# sw63_mk3.net
KiCad netlist of a schematic drawn in EAGLE
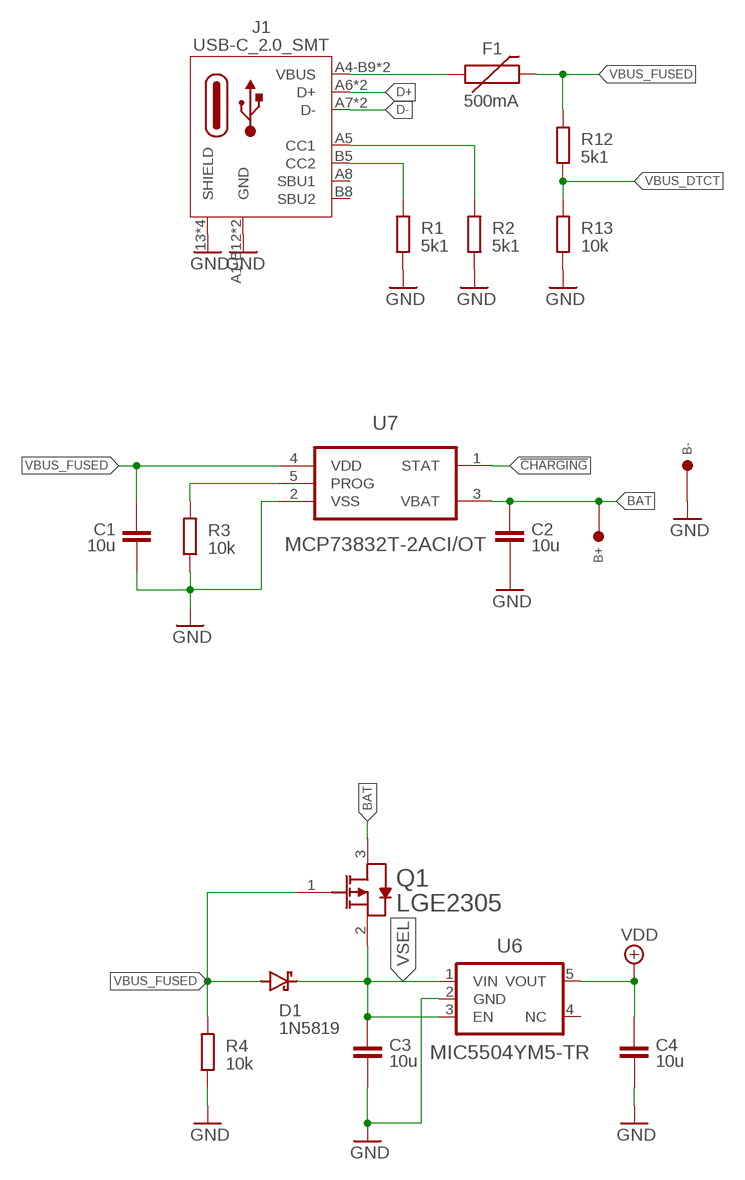
[diagram p0: schematic, sheet 1, part 1 of 2]
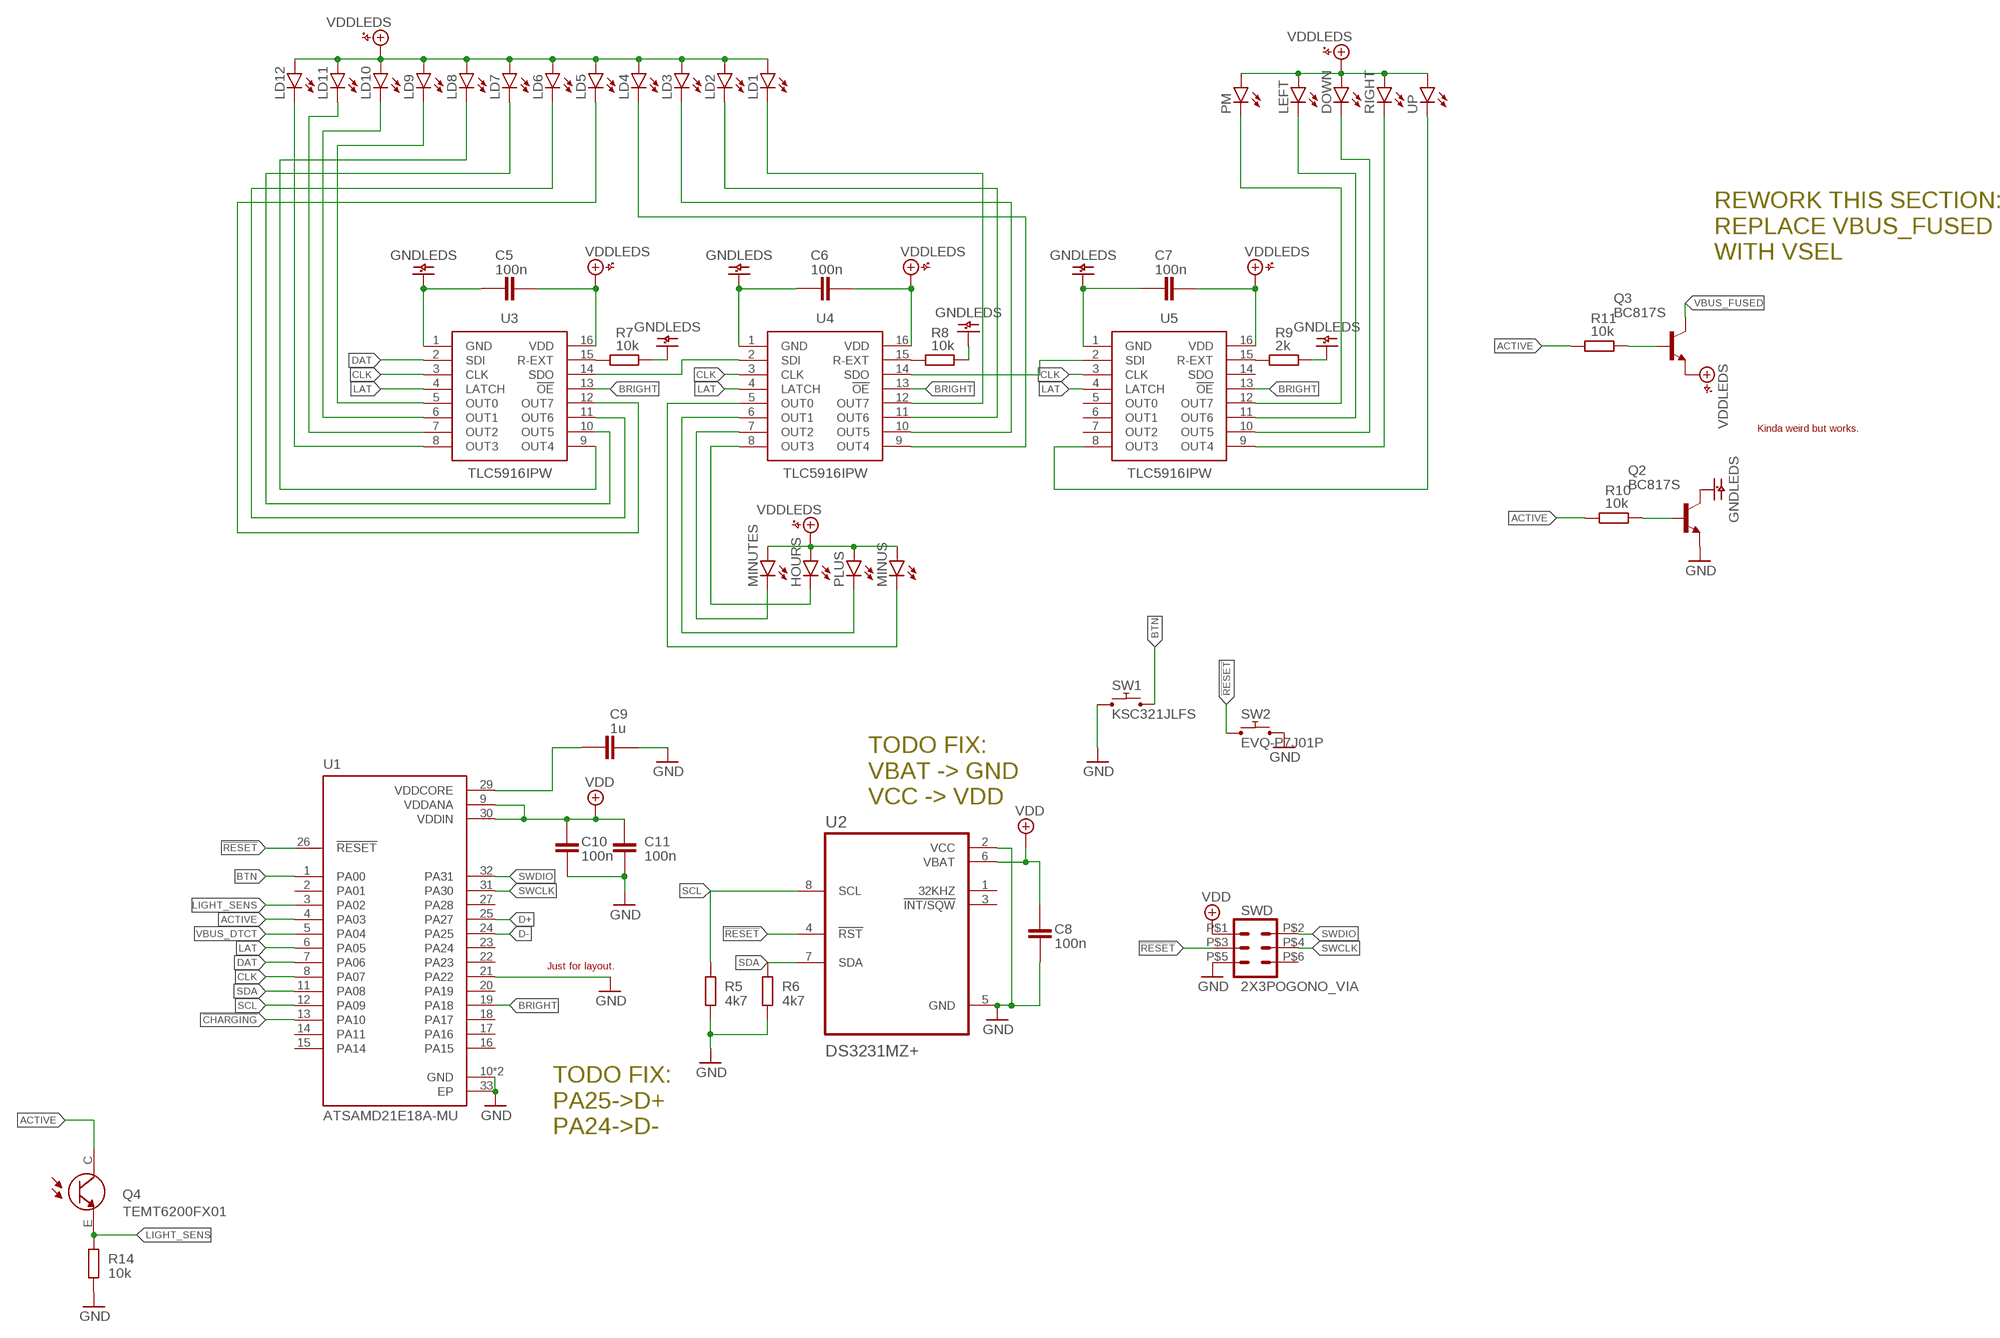
[diagram p1: schematic, sheet 1, part 2 of 2]

(export (version "E")
  (design (tool "Eeschema 10.0.6"))
  (components
    (comp (ref "B+")
      (value "TEST_PIN_LARGE")
      (footprint "eagle-import:TEST_PIN_2.0")
      (libsource (lib "eagle-import") (part "TEST_PIN_LARGE"))
    )
    (comp (ref "B-")
      (value "TEST_PIN_LARGE")
      (footprint "eagle-import:TEST_PIN_2.0")
      (libsource (lib "eagle-import") (part "TEST_PIN_LARGE"))
    )
    (comp (ref "C1")
      (value "10u")
      (footprint "eagle-import:CAPACITOR0805")
      (libsource (lib "eagle-import") (part "CAPACITOR0805"))
    )
    (comp (ref "C2")
      (value "10u")
      (footprint "eagle-import:CAPACITOR0805")
      (libsource (lib "eagle-import") (part "CAPACITOR0805"))
    )
    (comp (ref "C3")
      (value "10u")
      (footprint "eagle-import:CAPACITOR0805")
      (libsource (lib "eagle-import") (part "CAPACITOR0805"))
    )
    (comp (ref "C4")
      (value "10u")
      (footprint "eagle-import:CAPACITOR0805")
      (libsource (lib "eagle-import") (part "CAPACITOR0805"))
    )
    (comp (ref "C5")
      (value "100n")
      (footprint "eagle-import:CAPACITOR0603")
      (libsource (lib "eagle-import") (part "CAPACITOR0603"))
    )
    (comp (ref "C6")
      (value "100n")
      (footprint "eagle-import:CAPACITOR0603")
      (libsource (lib "eagle-import") (part "CAPACITOR0603"))
    )
    (comp (ref "C7")
      (value "100n")
      (footprint "eagle-import:CAPACITOR0603")
      (libsource (lib "eagle-import") (part "CAPACITOR0603"))
    )
    (comp (ref "C8")
      (value "100n")
      (footprint "eagle-import:CAPACITOR0603")
      (libsource (lib "eagle-import") (part "CAPACITOR0603"))
    )
    (comp (ref "C9")
      (value "1u")
      (footprint "eagle-import:CAPACITOR0603")
      (libsource (lib "eagle-import") (part "CAPACITOR0603"))
    )
    (comp (ref "C10")
      (value "100n")
      (footprint "eagle-import:CAPACITOR0603")
      (libsource (lib "eagle-import") (part "CAPACITOR0603"))
    )
    (comp (ref "C11")
      (value "100n")
      (footprint "eagle-import:CAPACITOR0603")
      (libsource (lib "eagle-import") (part "CAPACITOR0603"))
    )
    (comp (ref "D1")
      (value "1N5819")
      (footprint "eagle-import:SOD123")
      (libsource (lib "eagle-import") (part "SCHOTTKY_DIODE"))
    )
    (comp (ref "DOWN")
      (value "LED_RECT-3.2X2")
      (footprint "eagle-import:LED_RECT_3.2X2")
      (libsource (lib "eagle-import") (part "LED_RECT-3.2X2"))
    )
    (comp (ref "F1")
      (value "500mA")
      (footprint "eagle-import:PTC0805")
      (libsource (lib "eagle-import") (part "PTC"))
    )
    (comp (ref "HOURS")
      (value "LED_THT-5MM_B")
      (footprint "eagle-import:LED_5MM_BLUE")
      (libsource (lib "eagle-import") (part "LED_THT-5MM_B"))
    )
    (comp (ref "J1")
      (value "USB-C_2.0_SMT")
      (footprint "eagle-import:USB-C_FULL_SMT")
      (libsource (lib "eagle-import") (part "USB-C_2.0_SMT"))
    )
    (comp (ref "LD1")
      (value "LED_SMT_1206")
      (footprint "eagle-import:LED_1206")
      (libsource (lib "eagle-import") (part "LED_SMT_1206"))
    )
    (comp (ref "LD2")
      (value "LED_SMT_1206")
      (footprint "eagle-import:LED_1206")
      (libsource (lib "eagle-import") (part "LED_SMT_1206"))
    )
    (comp (ref "LD3")
      (value "LED_SMT_1206")
      (footprint "eagle-import:LED_1206")
      (libsource (lib "eagle-import") (part "LED_SMT_1206"))
    )
    (comp (ref "LD4")
      (value "LED_SMT_1206")
      (footprint "eagle-import:LED_1206")
      (libsource (lib "eagle-import") (part "LED_SMT_1206"))
    )
    (comp (ref "LD5")
      (value "LED_SMT_1206")
      (footprint "eagle-import:LED_1206")
      (libsource (lib "eagle-import") (part "LED_SMT_1206"))
    )
    (comp (ref "LD6")
      (value "LED_SMT_1206")
      (footprint "eagle-import:LED_1206")
      (libsource (lib "eagle-import") (part "LED_SMT_1206"))
    )
    (comp (ref "LD7")
      (value "LED_SMT_1206")
      (footprint "eagle-import:LED_1206")
      (libsource (lib "eagle-import") (part "LED_SMT_1206"))
    )
    (comp (ref "LD8")
      (value "LED_SMT_1206")
      (footprint "eagle-import:LED_1206")
      (libsource (lib "eagle-import") (part "LED_SMT_1206"))
    )
    (comp (ref "LD9")
      (value "LED_SMT_1206")
      (footprint "eagle-import:LED_1206")
      (libsource (lib "eagle-import") (part "LED_SMT_1206"))
    )
    (comp (ref "LD10")
      (value "LED_SMT_1206")
      (footprint "eagle-import:LED_1206")
      (libsource (lib "eagle-import") (part "LED_SMT_1206"))
    )
    (comp (ref "LD11")
      (value "LED_SMT_1206")
      (footprint "eagle-import:LED_1206")
      (libsource (lib "eagle-import") (part "LED_SMT_1206"))
    )
    (comp (ref "LD12")
      (value "LED_SMT_1206")
      (footprint "eagle-import:LED_1206")
      (libsource (lib "eagle-import") (part "LED_SMT_1206"))
    )
    (comp (ref "LEFT")
      (value "LED_RECT-3.2X2")
      (footprint "eagle-import:LED_RECT_3.2X2")
      (libsource (lib "eagle-import") (part "LED_RECT-3.2X2"))
    )
    (comp (ref "MINUS")
      (value "LED_THT-5MM_R")
      (footprint "eagle-import:LED_5MM_RED")
      (libsource (lib "eagle-import") (part "LED_THT-5MM_R"))
    )
    (comp (ref "MINUTES")
      (value "LED_THT-5MM_Y")
      (footprint "eagle-import:LED_5MM_YELLOW")
      (libsource (lib "eagle-import") (part "LED_THT-5MM_Y"))
    )
    (comp (ref "PLUS")
      (value "LED_THT-5MM_G")
      (footprint "eagle-import:LED_5MM_GREEN")
      (libsource (lib "eagle-import") (part "LED_THT-5MM_G"))
    )
    (comp (ref "PM")
      (value "LED_THT-3MM_ALT")
      (footprint "eagle-import:LED_3MM_ALT")
      (libsource (lib "eagle-import") (part "LED_THT-3MM_ALT"))
    )
    (comp (ref "Q1")
      (value "LGE2305")
      (footprint "eagle-import:SOT23")
      (libsource (lib "eagle-import") (part "LGE2305"))
    )
    (comp (ref "Q2")
      (value "BC817S")
      (footprint "eagle-import:SOT23")
      (libsource (lib "eagle-import") (part "BC817S"))
    )
    (comp (ref "Q3")
      (value "BC817S")
      (footprint "eagle-import:SOT23")
      (libsource (lib "eagle-import") (part "BC817S"))
    )
    (comp (ref "Q4")
      (value "TEMT6200FX01")
      (footprint "eagle-import:TEMT6200FX01")
      (fields (field (name "MF") "Vishay Semiconductor"))
      (libsource (lib "eagle-import") (part "TEMT6200FX01"))
    )
    (comp (ref "R1")
      (value "5k1")
      (footprint "eagle-import:RESISTOR0603")
      (libsource (lib "eagle-import") (part "RESISTOR0603"))
    )
    (comp (ref "R2")
      (value "5k1")
      (footprint "eagle-import:RESISTOR0603")
      (libsource (lib "eagle-import") (part "RESISTOR0603"))
    )
    (comp (ref "R3")
      (value "10k")
      (footprint "eagle-import:RESISTOR0603")
      (libsource (lib "eagle-import") (part "RESISTOR0603"))
    )
    (comp (ref "R4")
      (value "10k")
      (footprint "eagle-import:RESISTOR0603")
      (libsource (lib "eagle-import") (part "RESISTOR0603"))
    )
    (comp (ref "R5")
      (value "4k7")
      (footprint "eagle-import:RESISTOR0603")
      (libsource (lib "eagle-import") (part "RESISTOR0603"))
    )
    (comp (ref "R6")
      (value "4k7")
      (footprint "eagle-import:RESISTOR0603")
      (libsource (lib "eagle-import") (part "RESISTOR0603"))
    )
    (comp (ref "R7")
      (value "10k")
      (footprint "eagle-import:RESISTOR0603")
      (libsource (lib "eagle-import") (part "RESISTOR0603"))
    )
    (comp (ref "R8")
      (value "10k")
      (footprint "eagle-import:RESISTOR0603")
      (libsource (lib "eagle-import") (part "RESISTOR0603"))
    )
    (comp (ref "R9")
      (value "2k")
      (footprint "eagle-import:RESISTOR0603")
      (libsource (lib "eagle-import") (part "RESISTOR0603"))
    )
    (comp (ref "R10")
      (value "10k")
      (footprint "eagle-import:RESISTOR0603")
      (libsource (lib "eagle-import") (part "RESISTOR0603"))
    )
    (comp (ref "R11")
      (value "10k")
      (footprint "eagle-import:RESISTOR0603")
      (libsource (lib "eagle-import") (part "RESISTOR0603"))
    )
    (comp (ref "R12")
      (value "5k1")
      (footprint "eagle-import:RESISTOR0603")
      (libsource (lib "eagle-import") (part "RESISTOR0603"))
    )
    (comp (ref "R13")
      (value "10k")
      (footprint "eagle-import:RESISTOR0603")
      (libsource (lib "eagle-import") (part "RESISTOR0603"))
    )
    (comp (ref "R14")
      (value "10k")
      (footprint "eagle-import:RESISTOR0603")
      (libsource (lib "eagle-import") (part "RESISTOR0603"))
    )
    (comp (ref "RIGHT")
      (value "LED_RECT-3.2X2")
      (footprint "eagle-import:LED_RECT_3.2X2")
      (libsource (lib "eagle-import") (part "LED_RECT-3.2X2"))
    )
    (comp (ref "SW1")
      (value "KSC321JLFS")
      (footprint "eagle-import:KSC3XXJ")
      (libsource (lib "eagle-import") (part "KSC3XXJ"))
    )
    (comp (ref "SW2")
      (value "EVQ-P7J01P")
      (footprint "eagle-import:EVQ-P7J01P")
      (libsource (lib "eagle-import") (part "EVQ-P7J01P"))
    )
    (comp (ref "SWD")
      (value "2X3POGONO_VIA")
      (footprint "eagle-import:2X3_POGO_NO_VIA")
      (libsource (lib "eagle-import") (part "2X3POGONO_VIA"))
    )
    (comp (ref "U1")
      (value "ATSAMD21E18A-MU")
      (footprint "eagle-import:QFN50P500X500X100-33N")
      (fields (field (name "DIGIKEY_PART_NUMBER") "ATSAMD21E18A-MU-ND") (field (name "MF") "Microchip"))
      (libsource (lib "eagle-import") (part "ATSAMD21E18A-MU"))
    )
    (comp (ref "U2")
      (value "DS3231MZ+")
      (footprint "eagle-import:SO8")
      (fields
        (field (name "DIGI-KEY_PART_NUMBER") "DS3231MZ+-ND")
        (field (name "MF") "Maxim Integrated Products")
      )
      (libsource (lib "eagle-import") (part "DS3231MZ+"))
    )
    (comp (ref "U3")
      (value "TLC5916IPW")
      (footprint "eagle-import:TSSOP16")
      (libsource (lib "eagle-import") (part "TLC5916IPW"))
    )
    (comp (ref "U4")
      (value "TLC5916IPW")
      (footprint "eagle-import:TSSOP16")
      (libsource (lib "eagle-import") (part "TLC5916IPW"))
    )
    (comp (ref "U5")
      (value "TLC5916IPW")
      (footprint "eagle-import:TSSOP16")
      (libsource (lib "eagle-import") (part "TLC5916IPW"))
    )
    (comp (ref "U6")
      (value "MIC5504YM5-TR")
      (footprint "eagle-import:SOT23-5")
      (libsource (lib "eagle-import") (part "MIC5504YM5-TR"))
    )
    (comp (ref "U7")
      (value "MCP73832T-2ACI/OT")
      (footprint "eagle-import:SOT23-5")
      (fields (field (name "MPN") "MCP73831T-2ACI/OT"))
      (libsource (lib "eagle-import") (part "MCP73831T-2ACI"))
    )
    (comp (ref "UP")
      (value "LED_RECT-3.2X2")
      (footprint "eagle-import:LED_RECT_3.2X2")
      (libsource (lib "eagle-import") (part "LED_RECT-3.2X2"))
    )
  )
  (nets
    (net (code "1") (name "/~{CHARGING}") (class "Default")
      (node (ref "U1") (pin "13") (pinfunction "PA10_13") (pintype "bidirectional"))
      (node (ref "U7") (pin "1") (pinfunction "STAT_1") (pintype "output"))
    )
    (net (code "2") (name "/~{RESET}") (class "Default")
      (node (ref "SW2") (pin "1_1") (pinfunction "1_1_1") (pintype "passive"))
      (node (ref "SW2") (pin "1_2") (pinfunction "1_1_2") (pintype "passive"))
      (node (ref "SWD") (pin "P$3") (pinfunction "3_P$3") (pintype "passive"))
      (node (ref "U1") (pin "26") (pinfunction "~{RESET}_26") (pintype "input"))
      (node (ref "U2") (pin "4") (pinfunction "~{RST}_4") (pintype "bidirectional"))
    )
    (net (code "3") (name "ACTIVE") (class "Default")
      (node (ref "Q4") (pin "C") (pinfunction "C_C") (pintype "passive"))
      (node (ref "R10") (pin "2") (pinfunction "2_2") (pintype "passive"))
      (node (ref "R11") (pin "2") (pinfunction "2_2") (pintype "passive"))
      (node (ref "U1") (pin "4") (pinfunction "PA03_4") (pintype "bidirectional"))
    )
    (net (code "4") (name "BAT") (class "Default")
      (node (ref "B+") (pin "P$1") (pinfunction "P$1_P$1") (pintype "bidirectional"))
      (node (ref "C2") (pin "1") (pinfunction "1_1") (pintype "passive"))
      (node (ref "Q1") (pin "3") (pinfunction "DRAIN_3") (pintype "passive"))
      (node (ref "U7") (pin "3") (pinfunction "VBAT_3") (pintype "output"))
    )
    (net (code "5") (name "BRIGHT") (class "Default")
      (node (ref "U1") (pin "19") (pinfunction "PA18_19") (pintype "bidirectional"))
      (node (ref "U3") (pin "13") (pinfunction "~{OE}_13") (pintype "input"))
      (node (ref "U4") (pin "13") (pinfunction "~{OE}_13") (pintype "input"))
      (node (ref "U5") (pin "13") (pinfunction "~{OE}_13") (pintype "input"))
    )
    (net (code "6") (name "BTN") (class "Default")
      (node (ref "SW1") (pin "2") (pinfunction "2_2") (pintype "passive"))
      (node (ref "SW1") (pin "4") (pinfunction "2_4") (pintype "passive"))
      (node (ref "U1") (pin "1") (pinfunction "PA00_1") (pintype "bidirectional"))
    )
    (net (code "7") (name "CLK") (class "Default")
      (node (ref "U1") (pin "8") (pinfunction "PA07_8") (pintype "bidirectional"))
      (node (ref "U3") (pin "3") (pinfunction "CLK_3") (pintype "input"))
      (node (ref "U4") (pin "3") (pinfunction "CLK_3") (pintype "input"))
      (node (ref "U5") (pin "3") (pinfunction "CLK_3") (pintype "input"))
    )
    (net (code "8") (name "D+") (class "Default")
      (node (ref "J1") (pin "A6") (pinfunction "D+_A6") (pintype "bidirectional"))
      (node (ref "J1") (pin "B6") (pinfunction "D+_B6") (pintype "bidirectional"))
      (node (ref "U1") (pin "25") (pinfunction "PA27_25") (pintype "bidirectional"))
    )
    (net (code "9") (name "D-") (class "Default")
      (node (ref "J1") (pin "A7") (pinfunction "D-_A7") (pintype "bidirectional"))
      (node (ref "J1") (pin "B7") (pinfunction "D-_B7") (pintype "bidirectional"))
      (node (ref "U1") (pin "24") (pinfunction "PA25_24") (pintype "bidirectional"))
    )
    (net (code "10") (name "DAT") (class "Default")
      (node (ref "U1") (pin "7") (pinfunction "PA06_7") (pintype "bidirectional"))
      (node (ref "U3") (pin "2") (pinfunction "SDI_2") (pintype "input"))
    )
    (net (code "11") (name "GND") (class "Default")
      (node (ref "B-") (pin "P$1") (pinfunction "P$1_P$1") (pintype "bidirectional"))
      (node (ref "C1") (pin "2") (pinfunction "2_2") (pintype "passive"))
      (node (ref "C10") (pin "1") (pinfunction "1_1") (pintype "passive"))
      (node (ref "C11") (pin "1") (pinfunction "1_1") (pintype "passive"))
      (node (ref "C2") (pin "2") (pinfunction "2_2") (pintype "passive"))
      (node (ref "C3") (pin "2") (pinfunction "2_2") (pintype "passive"))
      (node (ref "C4") (pin "2") (pinfunction "2_2") (pintype "passive"))
      (node (ref "C8") (pin "2") (pinfunction "2_2") (pintype "passive"))
      (node (ref "C9") (pin "1") (pinfunction "1_1") (pintype "passive"))
      (node (ref "J1") (pin "13") (pinfunction "SHIELD_13") (pintype "bidirectional"))
      (node (ref "J1") (pin "14") (pinfunction "SHIELD_14") (pintype "bidirectional"))
      (node (ref "J1") (pin "15") (pinfunction "SHIELD_15") (pintype "bidirectional"))
      (node (ref "J1") (pin "16") (pinfunction "SHIELD_16") (pintype "bidirectional"))
      (node (ref "J1") (pin "A1-B12") (pinfunction "GND_A1-B12") (pintype "passive"))
      (node (ref "J1") (pin "B1-A12") (pinfunction "GND_B1-A12") (pintype "passive"))
      (node (ref "Q2") (pin "2") (pinfunction "E_2") (pintype "passive"))
      (node (ref "R1") (pin "1") (pinfunction "1_1") (pintype "passive"))
      (node (ref "R13") (pin "1") (pinfunction "1_1") (pintype "passive"))
      (node (ref "R14") (pin "1") (pinfunction "1_1") (pintype "passive"))
      (node (ref "R2") (pin "1") (pinfunction "1_1") (pintype "passive"))
      (node (ref "R3") (pin "1") (pinfunction "1_1") (pintype "passive"))
      (node (ref "R4") (pin "1") (pinfunction "1_1") (pintype "passive"))
      (node (ref "R5") (pin "1") (pinfunction "1_1") (pintype "passive"))
      (node (ref "R6") (pin "1") (pinfunction "1_1") (pintype "passive"))
      (node (ref "SW1") (pin "1") (pinfunction "1_1") (pintype "passive"))
      (node (ref "SW1") (pin "3") (pinfunction "1_3") (pintype "passive"))
      (node (ref "SW2") (pin "2_1") (pinfunction "2_2_1") (pintype "passive"))
      (node (ref "SW2") (pin "2_2") (pinfunction "2_2_2") (pintype "passive"))
      (node (ref "SWD") (pin "P$5") (pinfunction "5_P$5") (pintype "passive"))
      (node (ref "U1") (pin "10") (pinfunction "GND_10") (pintype "power_in"))
      (node (ref "U1") (pin "21") (pinfunction "PA22_21") (pintype "bidirectional"))
      (node (ref "U1") (pin "28") (pinfunction "GND_28") (pintype "power_in"))
      (node (ref "U1") (pin "33") (pinfunction "EP_33") (pintype "power_in"))
      (node (ref "U2") (pin "2") (pinfunction "VCC_2") (pintype "power_in"))
      (node (ref "U2") (pin "5") (pinfunction "GND_5") (pintype "power_in"))
      (node (ref "U6") (pin "2") (pinfunction "GND_2") (pintype "power_in"))
      (node (ref "U7") (pin "2") (pinfunction "VSS_2") (pintype "power_in"))
    )
    (net (code "12") (name "GNDLEDS") (class "Default")
      (node (ref "C5") (pin "1") (pinfunction "1_1") (pintype "passive"))
      (node (ref "C6") (pin "1") (pinfunction "1_1") (pintype "passive"))
      (node (ref "C7") (pin "1") (pinfunction "1_1") (pintype "passive"))
      (node (ref "Q2") (pin "3") (pinfunction "C_3") (pintype "passive"))
      (node (ref "R7") (pin "1") (pinfunction "1_1") (pintype "passive"))
      (node (ref "R8") (pin "1") (pinfunction "1_1") (pintype "passive"))
      (node (ref "R9") (pin "1") (pinfunction "1_1") (pintype "passive"))
      (node (ref "U3") (pin "1") (pinfunction "GND_1") (pintype "power_in"))
      (node (ref "U4") (pin "1") (pinfunction "GND_1") (pintype "power_in"))
      (node (ref "U5") (pin "1") (pinfunction "GND_1") (pintype "power_in"))
    )
    (net (code "13") (name "LAT") (class "Default")
      (node (ref "U1") (pin "6") (pinfunction "PA05_6") (pintype "bidirectional"))
      (node (ref "U3") (pin "4") (pinfunction "LATCH_4") (pintype "input"))
      (node (ref "U4") (pin "4") (pinfunction "LATCH_4") (pintype "input"))
      (node (ref "U5") (pin "4") (pinfunction "LATCH_4") (pintype "input"))
    )
    (net (code "14") (name "LIGHT_SENS") (class "Default")
      (node (ref "Q4") (pin "E") (pinfunction "E_E") (pintype "passive"))
      (node (ref "R14") (pin "2") (pinfunction "2_2") (pintype "passive"))
      (node (ref "U1") (pin "3") (pinfunction "PA02_3") (pintype "bidirectional"))
    )
    (net (code "15") (name "Net-(DOWN-C)") (class "Default")
      (node (ref "DOWN") (pin "K") (pinfunction "C_K") (pintype "passive"))
      (node (ref "U5") (pin "10") (pinfunction "OUT5_10") (pintype "output"))
    )
    (net (code "16") (name "Net-(F1-1)") (class "Default")
      (node (ref "F1") (pin "2") (pinfunction "1_2") (pintype "bidirectional"))
      (node (ref "J1") (pin "A4-B9") (pinfunction "VBUS_A4-B9") (pintype "power_in"))
      (node (ref "J1") (pin "B4-A9") (pinfunction "VBUS_B4-A9") (pintype "power_in"))
    )
    (net (code "17") (name "Net-(HOURS-C)") (class "Default")
      (node (ref "HOURS") (pin "K") (pinfunction "C_K") (pintype "passive"))
      (node (ref "U4") (pin "8") (pinfunction "OUT3_8") (pintype "output"))
    )
    (net (code "18") (name "Net-(J1-CC1)") (class "Default")
      (node (ref "J1") (pin "A5") (pinfunction "CC1_A5") (pintype "bidirectional"))
      (node (ref "R2") (pin "2") (pinfunction "2_2") (pintype "passive"))
    )
    (net (code "19") (name "Net-(J1-CC2)") (class "Default")
      (node (ref "J1") (pin "B5") (pinfunction "CC2_B5") (pintype "bidirectional"))
      (node (ref "R1") (pin "2") (pinfunction "2_2") (pintype "passive"))
    )
    (net (code "20") (name "Net-(LEFT-C)") (class "Default")
      (node (ref "LEFT") (pin "K") (pinfunction "C_K") (pintype "passive"))
      (node (ref "U5") (pin "11") (pinfunction "OUT6_11") (pintype "output"))
    )
    (net (code "21") (name "Net-(MINUS-C)") (class "Default")
      (node (ref "MINUS") (pin "K") (pinfunction "C_K") (pintype "passive"))
      (node (ref "U4") (pin "5") (pinfunction "OUT0_5") (pintype "output"))
    )
    (net (code "22") (name "Net-(MINUTES-C)") (class "Default")
      (node (ref "MINUTES") (pin "K") (pinfunction "C_K") (pintype "passive"))
      (node (ref "U4") (pin "7") (pinfunction "OUT2_7") (pintype "output"))
    )
    (net (code "23") (name "Net-(PLUS-C)") (class "Default")
      (node (ref "PLUS") (pin "K") (pinfunction "C_K") (pintype "passive"))
      (node (ref "U4") (pin "6") (pinfunction "OUT1_6") (pintype "output"))
    )
    (net (code "24") (name "Net-(PM-C)") (class "Default")
      (node (ref "PM") (pin "K") (pinfunction "C_K") (pintype "passive"))
      (node (ref "U5") (pin "12") (pinfunction "OUT7_12") (pintype "output"))
    )
    (net (code "25") (name "Net-(Q2-B)") (class "Default")
      (node (ref "Q2") (pin "1") (pinfunction "B_1") (pintype "passive"))
      (node (ref "R10") (pin "1") (pinfunction "1_1") (pintype "passive"))
    )
    (net (code "26") (name "Net-(Q3-B)") (class "Default")
      (node (ref "Q3") (pin "1") (pinfunction "B_1") (pintype "passive"))
      (node (ref "R11") (pin "1") (pinfunction "1_1") (pintype "passive"))
    )
    (net (code "27") (name "Net-(RIGHT-C)") (class "Default")
      (node (ref "RIGHT") (pin "K") (pinfunction "C_K") (pintype "passive"))
      (node (ref "U5") (pin "9") (pinfunction "OUT4_9") (pintype "output"))
    )
    (net (code "28") (name "Net-(U1-VDDCORE)") (class "Default")
      (node (ref "C9") (pin "2") (pinfunction "2_2") (pintype "passive"))
      (node (ref "U1") (pin "29") (pinfunction "VDDCORE_29") (pintype "power_in"))
    )
    (net (code "29") (name "Net-(U3-OUT0)") (class "Default")
      (node (ref "LD9") (pin "C") (pinfunction "C_C") (pintype "passive"))
      (node (ref "U3") (pin "5") (pinfunction "OUT0_5") (pintype "output"))
    )
    (net (code "30") (name "Net-(U3-OUT1)") (class "Default")
      (node (ref "LD10") (pin "C") (pinfunction "C_C") (pintype "passive"))
      (node (ref "U3") (pin "6") (pinfunction "OUT1_6") (pintype "output"))
    )
    (net (code "31") (name "Net-(U3-OUT2)") (class "Default")
      (node (ref "LD11") (pin "C") (pinfunction "C_C") (pintype "passive"))
      (node (ref "U3") (pin "7") (pinfunction "OUT2_7") (pintype "output"))
    )
    (net (code "32") (name "Net-(U3-OUT3)") (class "Default")
      (node (ref "LD12") (pin "C") (pinfunction "C_C") (pintype "passive"))
      (node (ref "U3") (pin "8") (pinfunction "OUT3_8") (pintype "output"))
    )
    (net (code "33") (name "Net-(U3-OUT4)") (class "Default")
      (node (ref "LD8") (pin "C") (pinfunction "C_C") (pintype "passive"))
      (node (ref "U3") (pin "9") (pinfunction "OUT4_9") (pintype "output"))
    )
    (net (code "34") (name "Net-(U3-OUT5)") (class "Default")
      (node (ref "LD7") (pin "C") (pinfunction "C_C") (pintype "passive"))
      (node (ref "U3") (pin "10") (pinfunction "OUT5_10") (pintype "output"))
    )
    (net (code "35") (name "Net-(U3-OUT6)") (class "Default")
      (node (ref "LD6") (pin "C") (pinfunction "C_C") (pintype "passive"))
      (node (ref "U3") (pin "11") (pinfunction "OUT6_11") (pintype "output"))
    )
    (net (code "36") (name "Net-(U3-OUT7)") (class "Default")
      (node (ref "LD5") (pin "C") (pinfunction "C_C") (pintype "passive"))
      (node (ref "U3") (pin "12") (pinfunction "OUT7_12") (pintype "output"))
    )
    (net (code "37") (name "Net-(U3-R-EXT)") (class "Default")
      (node (ref "R7") (pin "2") (pinfunction "2_2") (pintype "passive"))
      (node (ref "U3") (pin "15") (pinfunction "R-EXT_15") (pintype "input"))
    )
    (net (code "38") (name "Net-(U3-SDO)") (class "Default")
      (node (ref "U3") (pin "14") (pinfunction "SDO_14") (pintype "output"))
      (node (ref "U4") (pin "2") (pinfunction "SDI_2") (pintype "input"))
    )
    (net (code "39") (name "Net-(U4-OUT4)") (class "Default")
      (node (ref "LD4") (pin "C") (pinfunction "C_C") (pintype "passive"))
      (node (ref "U4") (pin "9") (pinfunction "OUT4_9") (pintype "output"))
    )
    (net (code "40") (name "Net-(U4-OUT5)") (class "Default")
      (node (ref "LD3") (pin "C") (pinfunction "C_C") (pintype "passive"))
      (node (ref "U4") (pin "10") (pinfunction "OUT5_10") (pintype "output"))
    )
    (net (code "41") (name "Net-(U4-OUT6)") (class "Default")
      (node (ref "LD2") (pin "C") (pinfunction "C_C") (pintype "passive"))
      (node (ref "U4") (pin "11") (pinfunction "OUT6_11") (pintype "output"))
    )
    (net (code "42") (name "Net-(U4-OUT7)") (class "Default")
      (node (ref "LD1") (pin "C") (pinfunction "C_C") (pintype "passive"))
      (node (ref "U4") (pin "12") (pinfunction "OUT7_12") (pintype "output"))
    )
    (net (code "43") (name "Net-(U4-R-EXT)") (class "Default")
      (node (ref "R8") (pin "2") (pinfunction "2_2") (pintype "passive"))
      (node (ref "U4") (pin "15") (pinfunction "R-EXT_15") (pintype "input"))
    )
    (net (code "44") (name "Net-(U4-SDO)") (class "Default")
      (node (ref "U4") (pin "14") (pinfunction "SDO_14") (pintype "output"))
      (node (ref "U5") (pin "2") (pinfunction "SDI_2") (pintype "input"))
    )
    (net (code "45") (name "Net-(U5-OUT3)") (class "Default")
      (node (ref "U5") (pin "8") (pinfunction "OUT3_8") (pintype "output"))
      (node (ref "UP") (pin "K") (pinfunction "C_K") (pintype "passive"))
    )
    (net (code "46") (name "Net-(U5-R-EXT)") (class "Default")
      (node (ref "R9") (pin "2") (pinfunction "2_2") (pintype "passive"))
      (node (ref "U5") (pin "15") (pinfunction "R-EXT_15") (pintype "input"))
    )
    (net (code "47") (name "Net-(U7-PROG)") (class "Default")
      (node (ref "R3") (pin "2") (pinfunction "2_2") (pintype "passive"))
      (node (ref "U7") (pin "5") (pinfunction "PROG_5") (pintype "input"))
    )
    (net (code "48") (name "SCL") (class "Default")
      (node (ref "R5") (pin "2") (pinfunction "2_2") (pintype "passive"))
      (node (ref "U1") (pin "12") (pinfunction "PA09_12") (pintype "bidirectional"))
      (node (ref "U2") (pin "8") (pinfunction "SCL_8") (pintype "input"))
    )
    (net (code "49") (name "SDA") (class "Default")
      (node (ref "R6") (pin "2") (pinfunction "2_2") (pintype "passive"))
      (node (ref "U1") (pin "11") (pinfunction "PA08_11") (pintype "bidirectional"))
      (node (ref "U2") (pin "7") (pinfunction "SDA_7") (pintype "bidirectional"))
    )
    (net (code "50") (name "SWCLK") (class "Default")
      (node (ref "SWD") (pin "P$4") (pinfunction "4_P$4") (pintype "passive"))
      (node (ref "U1") (pin "31") (pinfunction "PA30_31") (pintype "bidirectional"))
    )
    (net (code "51") (name "SWDIO") (class "Default")
      (node (ref "SWD") (pin "P$2") (pinfunction "2_P$2") (pintype "passive"))
      (node (ref "U1") (pin "32") (pinfunction "PA31_32") (pintype "bidirectional"))
    )
    (net (code "52") (name "VBUS_DTCT") (class "Default")
      (node (ref "R12") (pin "1") (pinfunction "1_1") (pintype "passive"))
      (node (ref "R13") (pin "2") (pinfunction "2_2") (pintype "passive"))
      (node (ref "U1") (pin "5") (pinfunction "PA04_5") (pintype "bidirectional"))
    )
    (net (code "53") (name "VBUS_FUSED") (class "Default")
      (node (ref "C1") (pin "1") (pinfunction "1_1") (pintype "passive"))
      (node (ref "D1") (pin "A") (pinfunction "A_A") (pintype "passive"))
      (node (ref "F1") (pin "3") (pinfunction "2_3") (pintype "bidirectional"))
      (node (ref "Q1") (pin "1") (pinfunction "GATE_1") (pintype "passive"))
      (node (ref "Q3") (pin "3") (pinfunction "C_3") (pintype "passive"))
      (node (ref "R12") (pin "2") (pinfunction "2_2") (pintype "passive"))
      (node (ref "R4") (pin "2") (pinfunction "2_2") (pintype "passive"))
      (node (ref "U7") (pin "4") (pinfunction "VDD_4") (pintype "power_in"))
    )
    (net (code "54") (name "VDD") (class "Default")
      (node (ref "C10") (pin "2") (pinfunction "2_2") (pintype "passive"))
      (node (ref "C11") (pin "2") (pinfunction "2_2") (pintype "passive"))
      (node (ref "C4") (pin "1") (pinfunction "1_1") (pintype "passive"))
      (node (ref "C8") (pin "1") (pinfunction "1_1") (pintype "passive"))
      (node (ref "SWD") (pin "P$1") (pinfunction "1_P$1") (pintype "passive"))
      (node (ref "U1") (pin "30") (pinfunction "VDDIN_30") (pintype "power_in"))
      (node (ref "U1") (pin "9") (pinfunction "VDDANA_9") (pintype "power_in"))
      (node (ref "U2") (pin "6") (pinfunction "VBAT_6") (pintype "power_in"))
      (node (ref "U6") (pin "5") (pinfunction "VOUT_5") (pintype "input"))
    )
    (net (code "55") (name "VDDLEDS") (class "Default")
      (node (ref "C5") (pin "2") (pinfunction "2_2") (pintype "passive"))
      (node (ref "C6") (pin "2") (pinfunction "2_2") (pintype "passive"))
      (node (ref "C7") (pin "2") (pinfunction "2_2") (pintype "passive"))
      (node (ref "DOWN") (pin "A") (pinfunction "A_A") (pintype "passive"))
      (node (ref "HOURS") (pin "A") (pinfunction "A_A") (pintype "passive"))
      (node (ref "LD1") (pin "A") (pinfunction "A_A") (pintype "passive"))
      (node (ref "LD10") (pin "A") (pinfunction "A_A") (pintype "passive"))
      (node (ref "LD11") (pin "A") (pinfunction "A_A") (pintype "passive"))
      (node (ref "LD12") (pin "A") (pinfunction "A_A") (pintype "passive"))
      (node (ref "LD2") (pin "A") (pinfunction "A_A") (pintype "passive"))
      (node (ref "LD3") (pin "A") (pinfunction "A_A") (pintype "passive"))
      (node (ref "LD4") (pin "A") (pinfunction "A_A") (pintype "passive"))
      (node (ref "LD5") (pin "A") (pinfunction "A_A") (pintype "passive"))
      (node (ref "LD6") (pin "A") (pinfunction "A_A") (pintype "passive"))
      (node (ref "LD7") (pin "A") (pinfunction "A_A") (pintype "passive"))
      (node (ref "LD8") (pin "A") (pinfunction "A_A") (pintype "passive"))
      (node (ref "LD9") (pin "A") (pinfunction "A_A") (pintype "passive"))
      (node (ref "LEFT") (pin "A") (pinfunction "A_A") (pintype "passive"))
      (node (ref "MINUS") (pin "A") (pinfunction "A_A") (pintype "passive"))
      (node (ref "MINUTES") (pin "A") (pinfunction "A_A") (pintype "passive"))
      (node (ref "PLUS") (pin "A") (pinfunction "A_A") (pintype "passive"))
      (node (ref "PM") (pin "A") (pinfunction "A_A") (pintype "passive"))
      (node (ref "Q3") (pin "2") (pinfunction "E_2") (pintype "passive"))
      (node (ref "RIGHT") (pin "A") (pinfunction "A_A") (pintype "passive"))
      (node (ref "U3") (pin "16") (pinfunction "VDD_16") (pintype "power_in"))
      (node (ref "U4") (pin "16") (pinfunction "VDD_16") (pintype "power_in"))
      (node (ref "U5") (pin "16") (pinfunction "VDD_16") (pintype "power_in"))
      (node (ref "UP") (pin "A") (pinfunction "A_A") (pintype "passive"))
    )
    (net (code "56") (name "VSEL") (class "Default")
      (node (ref "C3") (pin "1") (pinfunction "1_1") (pintype "passive"))
      (node (ref "D1") (pin "C") (pinfunction "C_C") (pintype "passive"))
      (node (ref "Q1") (pin "2") (pinfunction "SOURCE_2") (pintype "passive"))
      (node (ref "U6") (pin "1") (pinfunction "VIN_1") (pintype "input"))
      (node (ref "U6") (pin "3") (pinfunction "EN_3") (pintype "input"))
    )
    (net (code "57") (name "unconnected-(J1-SBU1-PadA8)") (class "Default")
      (node (ref "J1") (pin "A8") (pinfunction "SBU1_A8") (pintype "bidirectional"))
    )
    (net (code "58") (name "unconnected-(J1-SBU2-PadB8)") (class "Default")
      (node (ref "J1") (pin "B8") (pinfunction "SBU2_B8") (pintype "bidirectional"))
    )
    (net (code "59") (name "unconnected-(SWD-6-PadP$6)") (class "Default")
      (node (ref "SWD") (pin "P$6") (pinfunction "6_P$6") (pintype "passive"))
    )
    (net (code "60") (name "unconnected-(U1-PA01-Pad2)") (class "Default")
      (node (ref "U1") (pin "2") (pinfunction "PA01_2") (pintype "bidirectional"))
    )
    (net (code "61") (name "unconnected-(U1-PA11-Pad14)") (class "Default")
      (node (ref "U1") (pin "14") (pinfunction "PA11_14") (pintype "bidirectional"))
    )
    (net (code "62") (name "unconnected-(U1-PA14-Pad15)") (class "Default")
      (node (ref "U1") (pin "15") (pinfunction "PA14_15") (pintype "bidirectional"))
    )
    (net (code "63") (name "unconnected-(U1-PA15-Pad16)") (class "Default")
      (node (ref "U1") (pin "16") (pinfunction "PA15_16") (pintype "bidirectional"))
    )
    (net (code "64") (name "unconnected-(U1-PA16-Pad17)") (class "Default")
      (node (ref "U1") (pin "17") (pinfunction "PA16_17") (pintype "bidirectional"))
    )
    (net (code "65") (name "unconnected-(U1-PA17-Pad18)") (class "Default")
      (node (ref "U1") (pin "18") (pinfunction "PA17_18") (pintype "bidirectional"))
    )
    (net (code "66") (name "unconnected-(U1-PA19-Pad20)") (class "Default")
      (node (ref "U1") (pin "20") (pinfunction "PA19_20") (pintype "bidirectional"))
    )
    (net (code "67") (name "unconnected-(U1-PA23-Pad22)") (class "Default")
      (node (ref "U1") (pin "22") (pinfunction "PA23_22") (pintype "bidirectional"))
    )
    (net (code "68") (name "unconnected-(U1-PA24-Pad23)") (class "Default")
      (node (ref "U1") (pin "23") (pinfunction "PA24_23") (pintype "bidirectional"))
    )
    (net (code "69") (name "unconnected-(U1-PA28-Pad27)") (class "Default")
      (node (ref "U1") (pin "27") (pinfunction "PA28_27") (pintype "bidirectional"))
    )
    (net (code "70") (name "unconnected-(U2-32KHZ-Pad1)") (class "Default")
      (node (ref "U2") (pin "1") (pinfunction "32KHZ_1") (pintype "output"))
    )
    (net (code "71") (name "unconnected-(U2-~{INT{slash}SQW}-Pad3)") (class "Default")
      (node (ref "U2") (pin "3") (pinfunction "~{INT/SQW}_3") (pintype "output"))
    )
    (net (code "72") (name "unconnected-(U5-OUT0-Pad5)") (class "Default")
      (node (ref "U5") (pin "5") (pinfunction "OUT0_5") (pintype "output"))
    )
    (net (code "73") (name "unconnected-(U5-OUT1-Pad6)") (class "Default")
      (node (ref "U5") (pin "6") (pinfunction "OUT1_6") (pintype "output"))
    )
    (net (code "74") (name "unconnected-(U5-OUT2-Pad7)") (class "Default")
      (node (ref "U5") (pin "7") (pinfunction "OUT2_7") (pintype "output"))
    )
    (net (code "75") (name "unconnected-(U5-SDO-Pad14)") (class "Default")
      (node (ref "U5") (pin "14") (pinfunction "SDO_14") (pintype "output"))
    )
    (net (code "76") (name "unconnected-(U6-NC-Pad4)") (class "Default")
      (node (ref "U6") (pin "4") (pinfunction "NC_4") (pintype "no_connect"))
    )
  )
)
